# MB786.net
KiCad netlist of a schematic drawn in Altium Designer
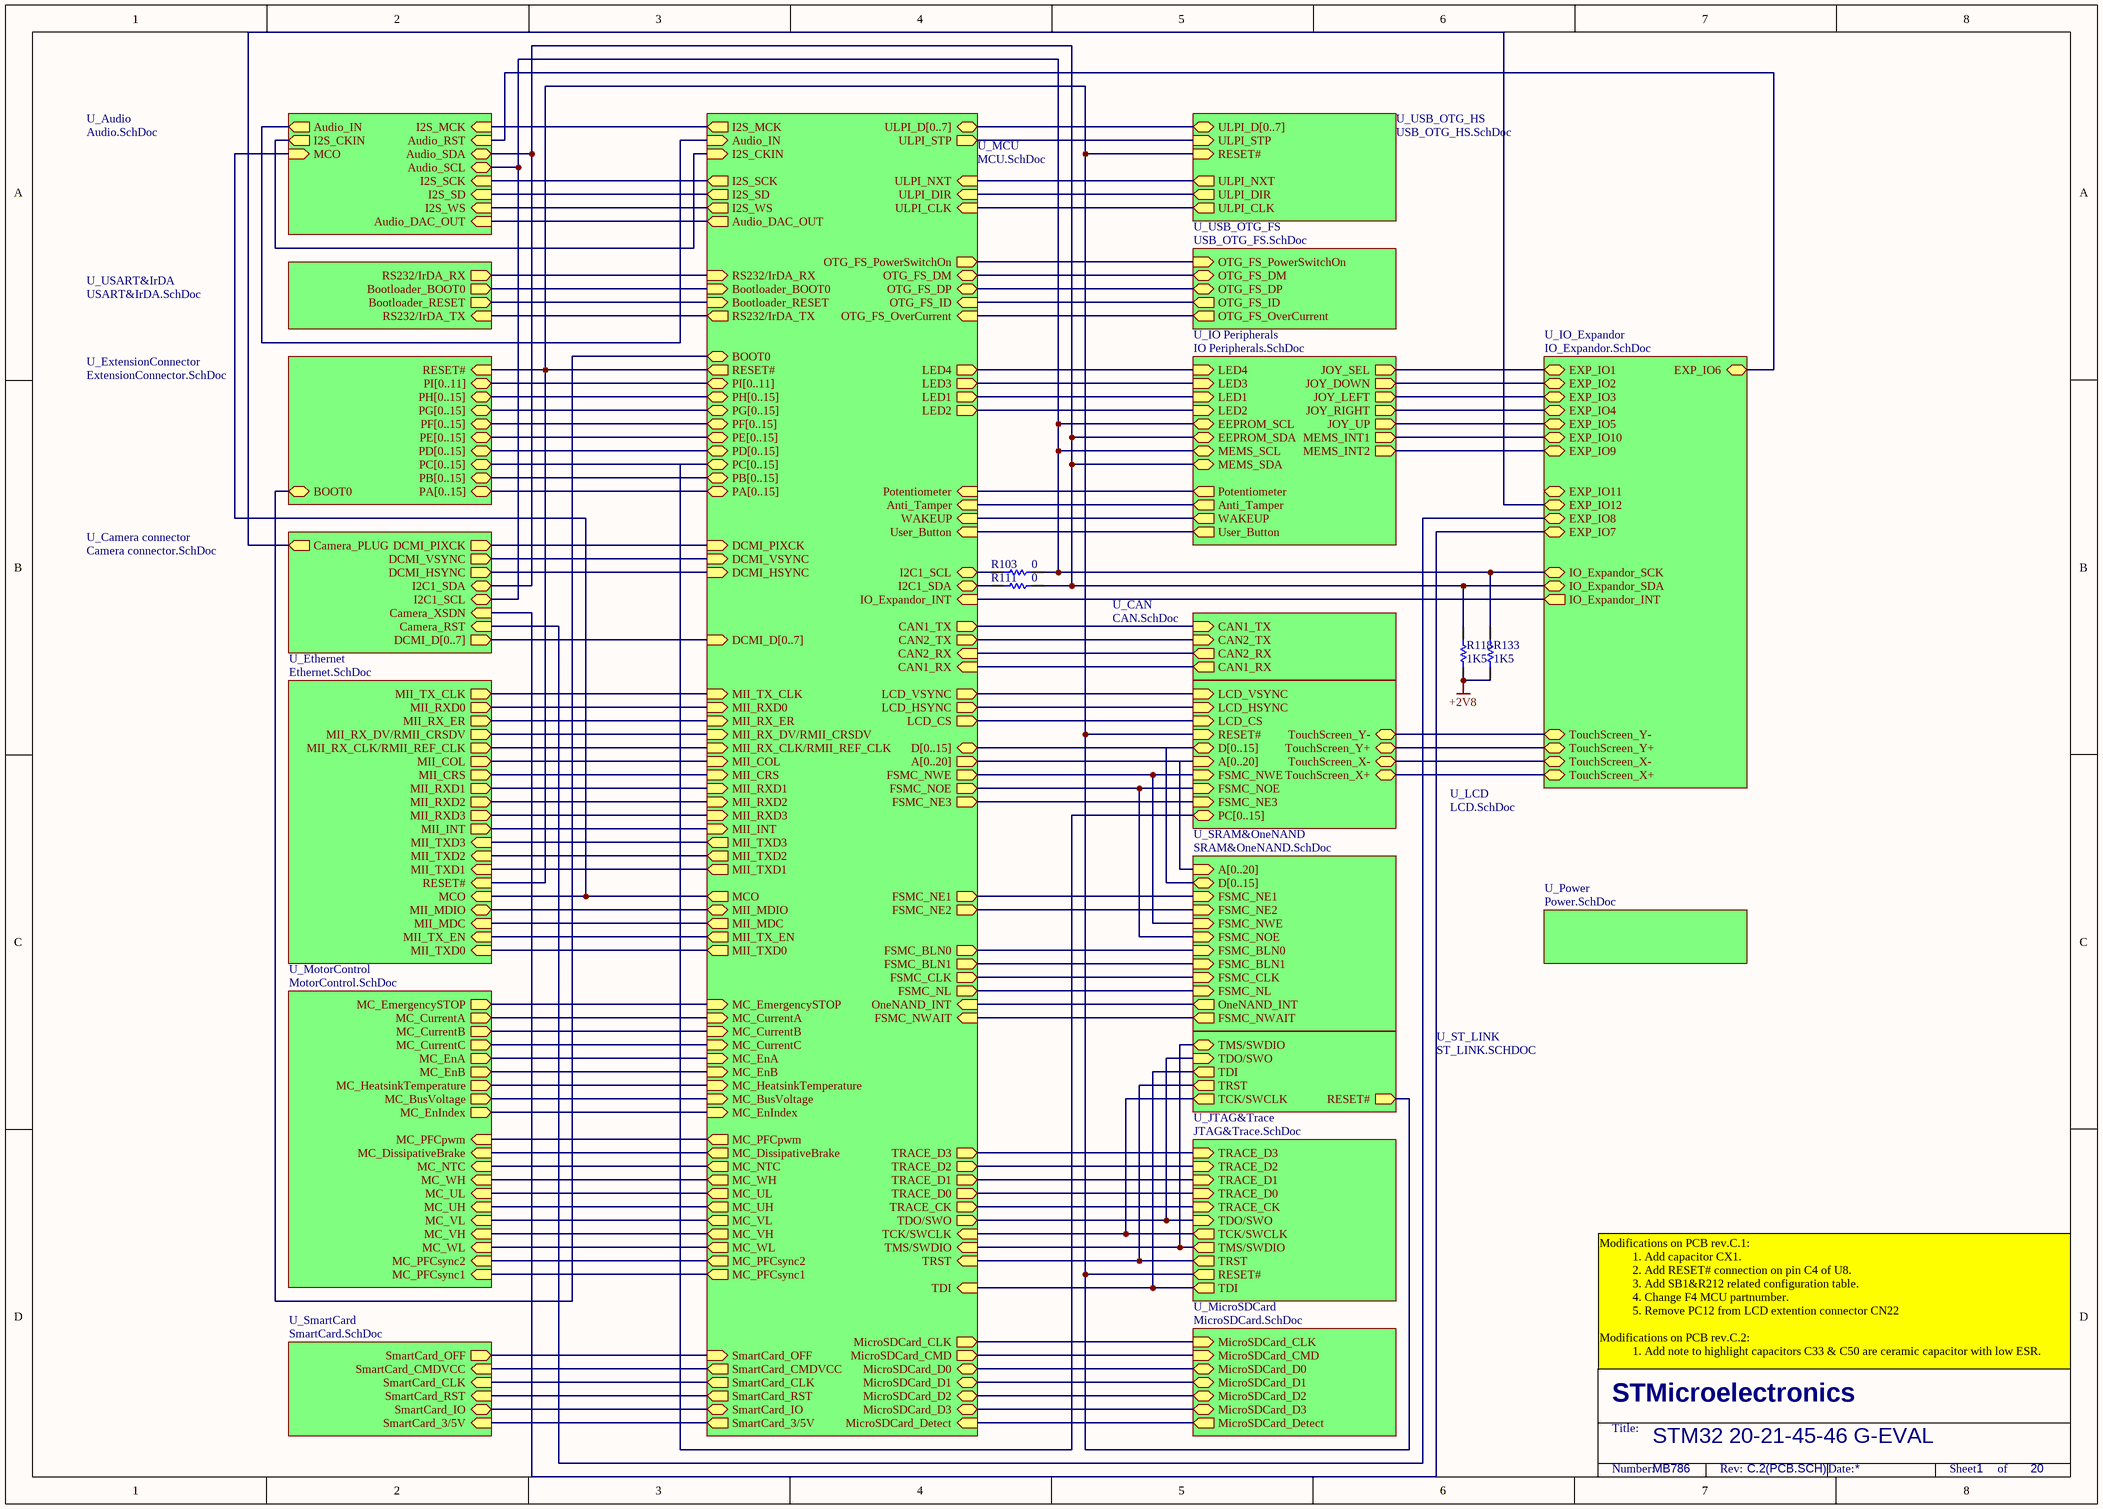
[diagram p0: MB786.SchDoc]

(export (version "E")
  (design (tool "Eeschema 10.0.6"))
  (components
    (comp (ref "R103")
      (value "0")
      (footprint "0603R")
      (description "Resistor")
      (fields (field (name "PUBLISHER") "Altium Limited"))
      (libsource (lib "Miscellaneous Devices") (part "Res1"))
    )
    (comp (ref "R111")
      (value "0")
      (footprint "0603R")
      (description "Resistor")
      (fields (field (name "PUBLISHER") "Altium Limited"))
      (libsource (lib "Miscellaneous Devices") (part "Res1"))
    )
    (comp (ref "R118")
      (value "1K5")
      (footprint "0603R")
      (description "Resistor")
      (fields (field (name "PUBLISHER") "Altium Limited"))
      (libsource (lib "Miscellaneous Devices") (part "Res1"))
    )
    (comp (ref "R133")
      (value "1K5")
      (footprint "0603R")
      (description "Resistor")
      (fields (field (name "PUBLISHER") "Altium Limited"))
      (libsource (lib "Miscellaneous Devices") (part "Res1"))
    )
  )
  (nets
    (net (code "1") (name "+2V8") (class "Default")
      (node (ref "R118") (pin "1") (pinfunction "1_1") (pintype "passive"))
      (node (ref "R133") (pin "1") (pinfunction "1_1") (pintype "passive"))
    )
    (net (code "8") (name "/Audio_SCL") (class "Default")
      (node (ref "R103") (pin "1") (pinfunction "1_1") (pintype "passive"))
      (node (ref "R133") (pin "2") (pinfunction "2_2") (pintype "passive"))
    )
    (net (code "9") (name "/Audio_SDA") (class "Default")
      (node (ref "R111") (pin "1") (pinfunction "1_1") (pintype "passive"))
      (node (ref "R118") (pin "2") (pinfunction "2_2") (pintype "passive"))
    )
    (net (code "37") (name "/I2C1_SCL") (class "Default")
      (node (ref "R103") (pin "2") (pinfunction "2_2") (pintype "passive"))
    )
    (net (code "38") (name "/I2C1_SDA") (class "Default")
      (node (ref "R111") (pin "2") (pinfunction "2_2") (pintype "passive"))
    )
  )
)
